# CarteMereM1_V2.net
KiCad netlist of a schematic drawn in EAGLE
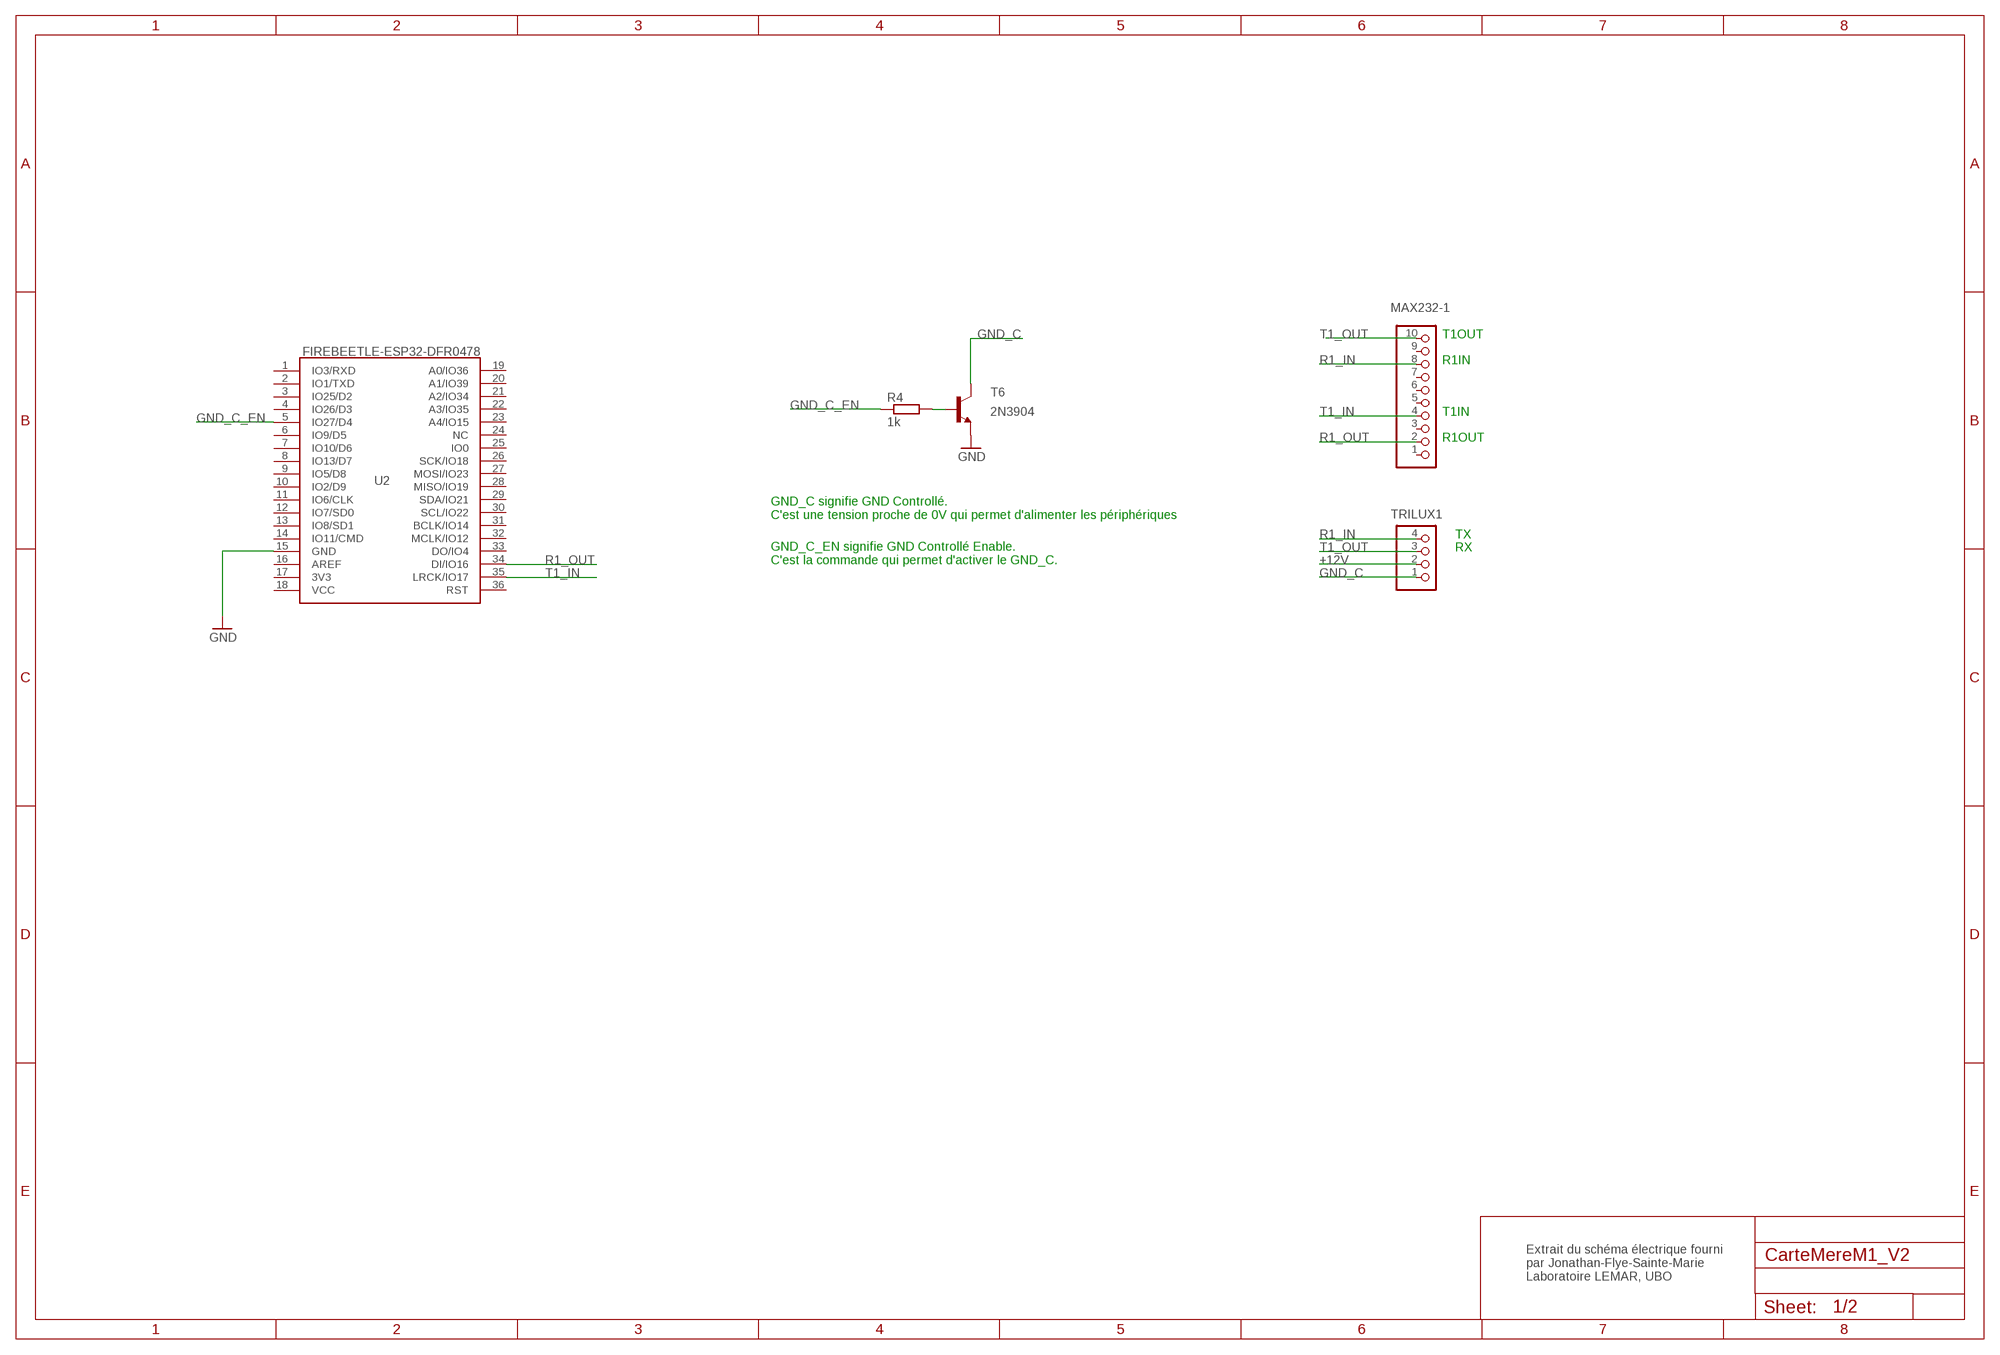
[diagram p0: schematic, sheet 1, part 1 of 2]
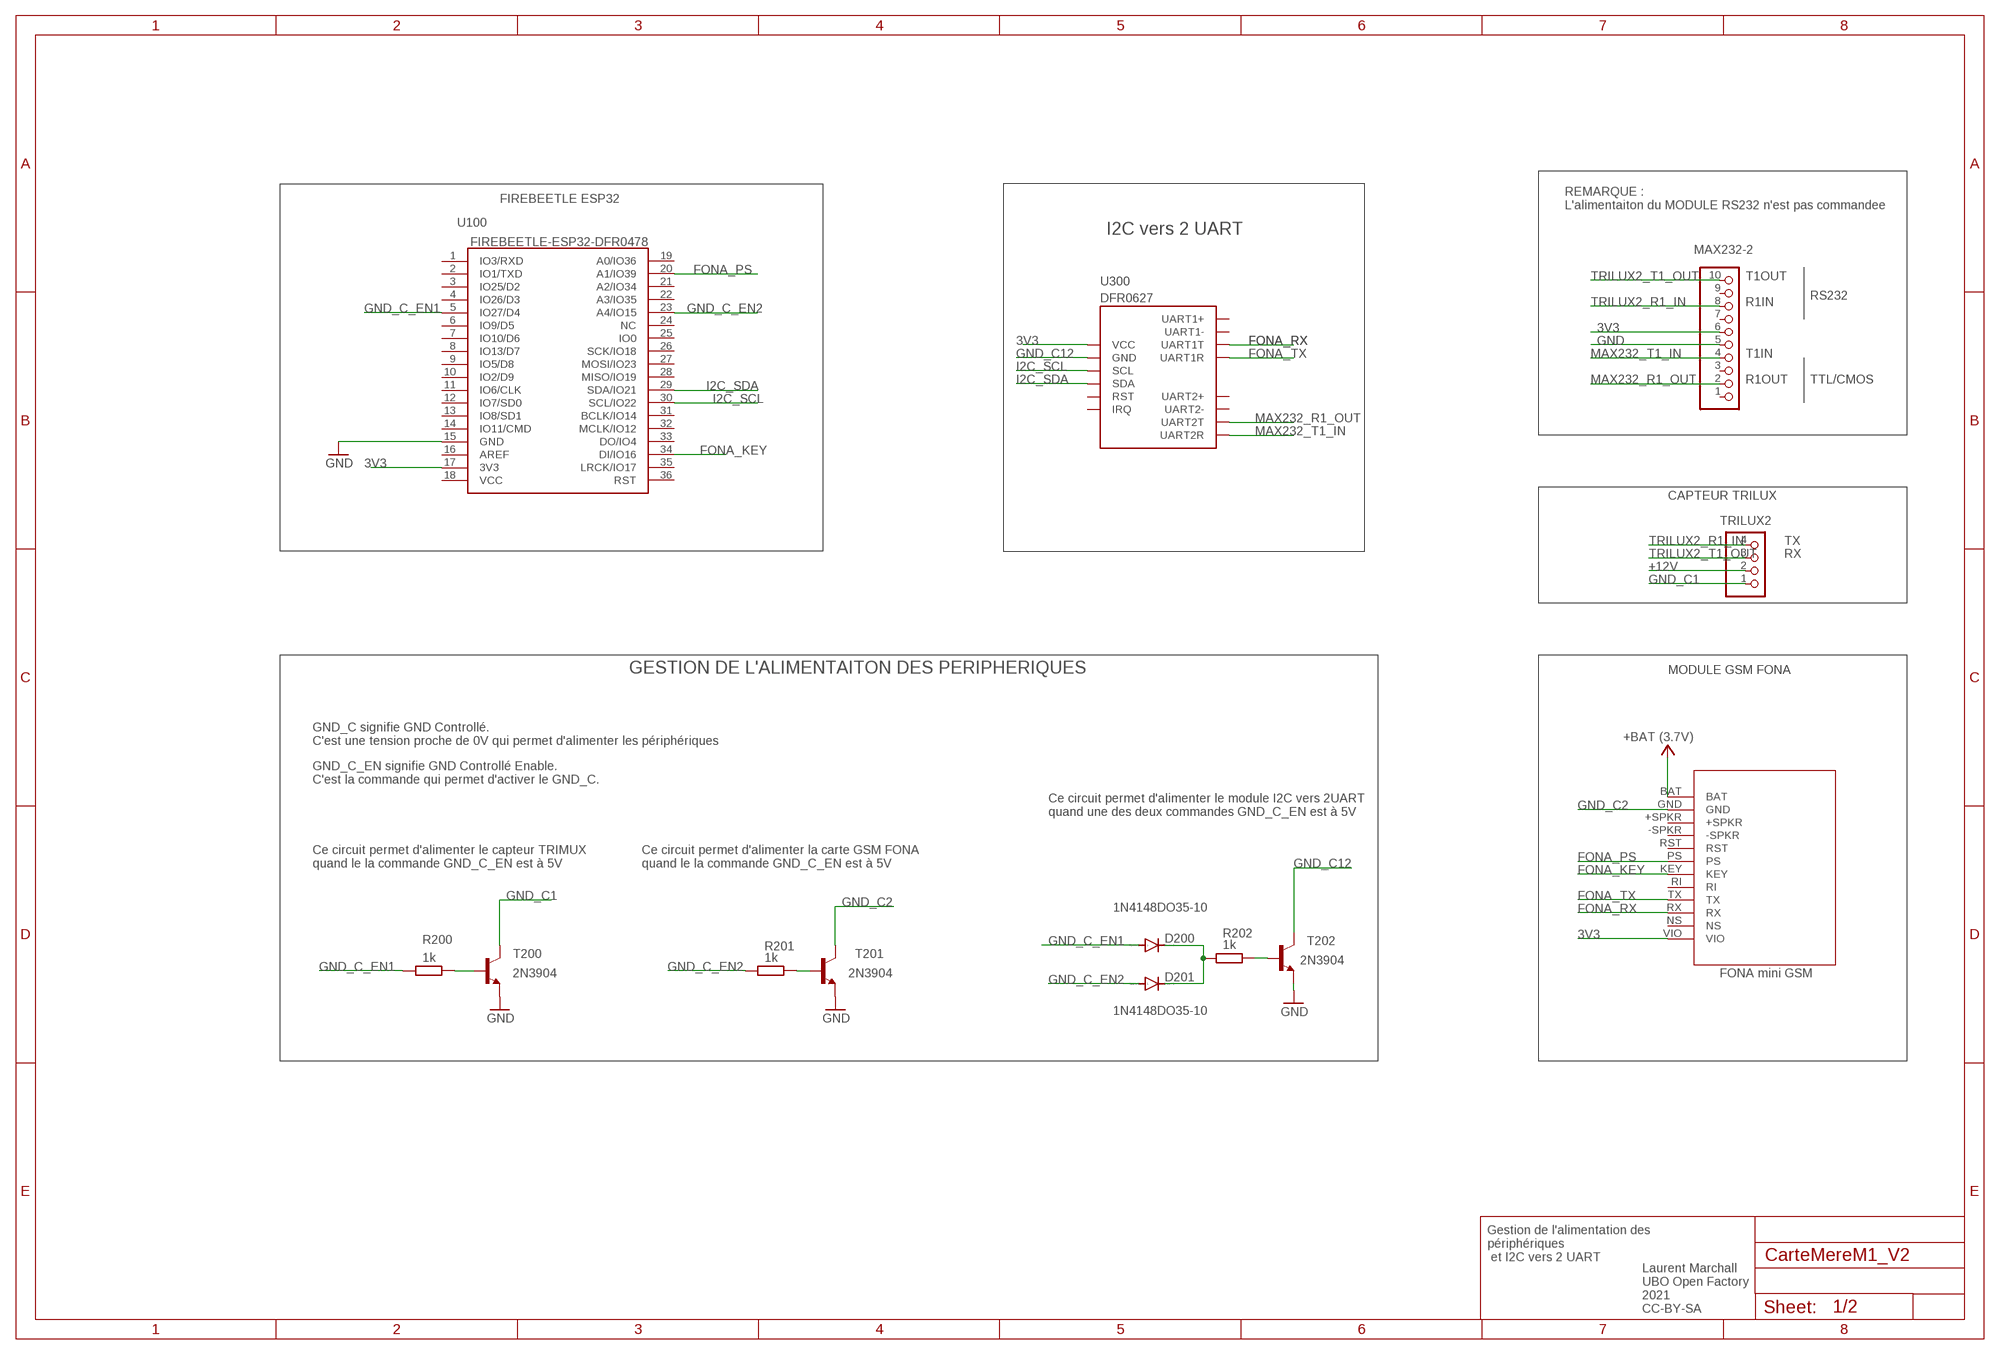
[diagram p1: schematic, sheet 1, part 2 of 2]

(export (version "E")
  (design (tool "Eeschema 10.0.6"))
  (components
    (comp (ref "D200")
      (value "1N4148DO35-10")
      (footprint "eagle-import:DO35-10")
      (libsource (lib "eagle-import") (part "1N4148DO35-10"))
    )
    (comp (ref "D201")
      (value "1N4148DO35-10")
      (footprint "eagle-import:DO35-10")
      (libsource (lib "eagle-import") (part "1N4148DO35-10"))
    )
    (comp (ref "MAX232-1")
      (value "PINHD-1X10")
      (footprint "eagle-import:1X10")
      (libsource (lib "eagle-import") (part "PINHD-1X10"))
    )
    (comp (ref "MAX232-2")
      (value "PINHD-1X10")
      (footprint "eagle-import:1X10")
      (libsource (lib "eagle-import") (part "PINHD-1X10"))
    )
    (comp (ref "R4")
      (value "1k")
      (footprint "eagle-import:0204_7")
      (libsource (lib "eagle-import") (part "R-EU_0204/7"))
    )
    (comp (ref "R200")
      (value "1k")
      (footprint "eagle-import:0204_7")
      (libsource (lib "eagle-import") (part "R-EU_0204/7"))
    )
    (comp (ref "R201")
      (value "1k")
      (footprint "eagle-import:0204_7")
      (libsource (lib "eagle-import") (part "R-EU_0204/7"))
    )
    (comp (ref "R202")
      (value "1k")
      (footprint "eagle-import:0204_7")
      (libsource (lib "eagle-import") (part "R-EU_0204/7"))
    )
    (comp (ref "T6")
      (value "2N3904")
      (footprint "eagle-import:TO92")
      (libsource (lib "eagle-import") (part "2N3904"))
    )
    (comp (ref "T200")
      (value "2N3904")
      (footprint "eagle-import:TO92")
      (libsource (lib "eagle-import") (part "2N3904"))
    )
    (comp (ref "T201")
      (value "2N3904")
      (footprint "eagle-import:TO92")
      (libsource (lib "eagle-import") (part "2N3904"))
    )
    (comp (ref "T202")
      (value "2N3904")
      (footprint "eagle-import:TO92")
      (libsource (lib "eagle-import") (part "2N3904"))
    )
    (comp (ref "TRILUX1")
      (value "PINHD-1X4")
      (footprint "eagle-import:1X04")
      (libsource (lib "eagle-import") (part "PINHD-1X4"))
    )
    (comp (ref "TRILUX2")
      (value "PINHD-1X4")
      (footprint "eagle-import:1X04")
      (libsource (lib "eagle-import") (part "PINHD-1X4"))
    )
    (comp (ref "U$1")
      (value "FONA_MINI_GSM")
      (footprint "eagle-import:FONA_MINI_GSM")
      (libsource (lib "eagle-import") (part "FONA_MINI_GSM"))
    )
    (comp (ref "U2")
      (value "FIREBEETLE-ESP32-DFR0478")
      (footprint "eagle-import:FIREBEETLE_ESP32")
      (fields
        (field (name "MANUFACTURER_PART_NUMBER") "DFR0478")
        (field (name "MOUSER_PART_NUMBER") "426-DFR0478")
      )
      (libsource (lib "eagle-import") (part "FIREBEETLE-ESP32-DFR0478"))
    )
    (comp (ref "U100")
      (value "FIREBEETLE-ESP32-DFR0478")
      (footprint "eagle-import:FIREBEETLE_ESP32")
      (fields
        (field (name "MANUFACTURER_PART_NUMBER") "DFR0478")
        (field (name "MOUSER_PART_NUMBER") "426-DFR0478")
      )
      (libsource (lib "eagle-import") (part "FIREBEETLE-ESP32-DFR0478"))
    )
    (comp (ref "U300")
      (value "DFR0627")
      (footprint "eagle-import:DUAL-UART-MODULE-DFR0627")
      (libsource (lib "eagle-import") (part "DUAL-UART-MODULE-DFR0627"))
    )
  )
  (nets
    (net (code "1") (name "+12V") (class "Default")
      (node (ref "TRILUX1") (pin "2") (pinfunction "2_2") (pintype "passive"))
      (node (ref "TRILUX2") (pin "2") (pinfunction "2_2") (pintype "passive"))
    )
    (net (code "2") (name "+BAT (3.7V)") (class "Default")
      (node (ref "U$1") (pin "BAT") (pinfunction "BAT_BAT") (pintype "power_in"))
    )
    (net (code "3") (name "3V3") (class "Default")
      (node (ref "MAX232-2") (pin "6") (pinfunction "6_6") (pintype "passive"))
      (node (ref "U$1") (pin "VIO") (pinfunction "VIO_VIO") (pintype "input"))
      (node (ref "U100") (pin "17") (pinfunction "3V3_17") (pintype "bidirectional"))
      (node (ref "U300") (pin "VCC") (pinfunction "VCC_VCC") (pintype "bidirectional"))
    )
    (net (code "4") (name "FONA_KEY") (class "Default")
      (node (ref "U$1") (pin "KEY") (pinfunction "KEY_KEY") (pintype "input"))
      (node (ref "U100") (pin "34") (pinfunction "DI/IO16_34") (pintype "bidirectional"))
    )
    (net (code "5") (name "FONA_PS") (class "Default")
      (node (ref "U$1") (pin "PS") (pinfunction "PS_PS") (pintype "output"))
      (node (ref "U100") (pin "20") (pinfunction "A1/IO39_20") (pintype "bidirectional"))
    )
    (net (code "6") (name "FONA_RX") (class "Default")
      (node (ref "U$1") (pin "RX") (pinfunction "RX_RX") (pintype "input"))
      (node (ref "U300") (pin "UART1T") (pinfunction "UART1T_UART1T") (pintype "bidirectional"))
    )
    (net (code "7") (name "FONA_TX") (class "Default")
      (node (ref "U$1") (pin "TX") (pinfunction "TX_TX") (pintype "output"))
      (node (ref "U300") (pin "UART1R") (pinfunction "UART1R_UART1R") (pintype "bidirectional"))
    )
    (net (code "8") (name "GND") (class "Default")
      (node (ref "MAX232-2") (pin "5") (pinfunction "5_5") (pintype "passive"))
      (node (ref "T200") (pin "3") (pinfunction "E_3") (pintype "passive"))
      (node (ref "T201") (pin "3") (pinfunction "E_3") (pintype "passive"))
      (node (ref "T202") (pin "3") (pinfunction "E_3") (pintype "passive"))
      (node (ref "T6") (pin "3") (pinfunction "E_3") (pintype "passive"))
      (node (ref "U100") (pin "15") (pinfunction "GND_15") (pintype "bidirectional"))
      (node (ref "U2") (pin "15") (pinfunction "GND_15") (pintype "bidirectional"))
    )
    (net (code "9") (name "GND_C") (class "Default")
      (node (ref "T6") (pin "1") (pinfunction "C_1") (pintype "passive"))
      (node (ref "TRILUX1") (pin "1") (pinfunction "1_1") (pintype "passive"))
    )
    (net (code "10") (name "GND_C1") (class "Default")
      (node (ref "T200") (pin "1") (pinfunction "C_1") (pintype "passive"))
      (node (ref "TRILUX2") (pin "1") (pinfunction "1_1") (pintype "passive"))
    )
    (net (code "11") (name "GND_C2") (class "Default")
      (node (ref "T201") (pin "1") (pinfunction "C_1") (pintype "passive"))
      (node (ref "U$1") (pin "GND") (pinfunction "GND_GND") (pintype "power_in"))
    )
    (net (code "12") (name "GND_C12") (class "Default")
      (node (ref "T202") (pin "1") (pinfunction "C_1") (pintype "passive"))
      (node (ref "U300") (pin "GND") (pinfunction "GND_GND") (pintype "bidirectional"))
    )
    (net (code "13") (name "GND_C_EN") (class "Default")
      (node (ref "R4") (pin "1") (pinfunction "1_1") (pintype "passive"))
      (node (ref "U2") (pin "5") (pinfunction "IO27/D4_5") (pintype "bidirectional"))
    )
    (net (code "14") (name "GND_C_EN1") (class "Default")
      (node (ref "D200") (pin "A") (pinfunction "A_A") (pintype "passive"))
      (node (ref "R200") (pin "1") (pinfunction "1_1") (pintype "passive"))
      (node (ref "U100") (pin "5") (pinfunction "IO27/D4_5") (pintype "bidirectional"))
    )
    (net (code "15") (name "GND_C_EN2") (class "Default")
      (node (ref "D201") (pin "A") (pinfunction "A_A") (pintype "passive"))
      (node (ref "R201") (pin "1") (pinfunction "1_1") (pintype "passive"))
      (node (ref "U100") (pin "23") (pinfunction "A4/IO15_23") (pintype "bidirectional"))
    )
    (net (code "16") (name "I2C_SCL") (class "Default")
      (node (ref "U100") (pin "30") (pinfunction "SCL/IO22_30") (pintype "bidirectional"))
      (node (ref "U300") (pin "SCL") (pinfunction "SCL_SCL") (pintype "bidirectional"))
    )
    (net (code "17") (name "I2C_SDA") (class "Default")
      (node (ref "U100") (pin "29") (pinfunction "SDA/IO21_29") (pintype "bidirectional"))
      (node (ref "U300") (pin "SDA") (pinfunction "SDA_SDA") (pintype "bidirectional"))
    )
    (net (code "18") (name "MAX232_R1_OUT") (class "Default")
      (node (ref "MAX232-2") (pin "2") (pinfunction "2_2") (pintype "passive"))
      (node (ref "U300") (pin "UART2T") (pinfunction "UART2T_UART2T") (pintype "bidirectional"))
    )
    (net (code "19") (name "MAX232_T1_IN") (class "Default")
      (node (ref "MAX232-2") (pin "4") (pinfunction "4_4") (pintype "passive"))
      (node (ref "U300") (pin "UART2R") (pinfunction "UART2R_UART2R") (pintype "bidirectional"))
    )
    (net (code "20") (name "Net-(D200-PadC)") (class "Default")
      (node (ref "D200") (pin "C") (pinfunction "C_C") (pintype "passive"))
      (node (ref "D201") (pin "C") (pinfunction "C_C") (pintype "passive"))
      (node (ref "R202") (pin "1") (pinfunction "1_1") (pintype "passive"))
    )
    (net (code "21") (name "Net-(T6-B)") (class "Default")
      (node (ref "R4") (pin "2") (pinfunction "2_2") (pintype "passive"))
      (node (ref "T6") (pin "2") (pinfunction "B_2") (pintype "passive"))
    )
    (net (code "22") (name "Net-(T200-B)") (class "Default")
      (node (ref "R200") (pin "2") (pinfunction "2_2") (pintype "passive"))
      (node (ref "T200") (pin "2") (pinfunction "B_2") (pintype "passive"))
    )
    (net (code "23") (name "Net-(T201-B)") (class "Default")
      (node (ref "R201") (pin "2") (pinfunction "2_2") (pintype "passive"))
      (node (ref "T201") (pin "2") (pinfunction "B_2") (pintype "passive"))
    )
    (net (code "24") (name "Net-(T202-B)") (class "Default")
      (node (ref "R202") (pin "2") (pinfunction "2_2") (pintype "passive"))
      (node (ref "T202") (pin "2") (pinfunction "B_2") (pintype "passive"))
    )
    (net (code "25") (name "R1_IN") (class "Default")
      (node (ref "MAX232-1") (pin "8") (pinfunction "8_8") (pintype "passive"))
      (node (ref "TRILUX1") (pin "4") (pinfunction "4_4") (pintype "passive"))
    )
    (net (code "26") (name "R1_OUT") (class "Default")
      (node (ref "MAX232-1") (pin "2") (pinfunction "2_2") (pintype "passive"))
      (node (ref "U2") (pin "34") (pinfunction "DI/IO16_34") (pintype "bidirectional"))
    )
    (net (code "27") (name "T1_IN") (class "Default")
      (node (ref "MAX232-1") (pin "4") (pinfunction "4_4") (pintype "passive"))
      (node (ref "U2") (pin "35") (pinfunction "LRCK/IO17_35") (pintype "bidirectional"))
    )
    (net (code "28") (name "T1_OUT") (class "Default")
      (node (ref "MAX232-1") (pin "10") (pinfunction "10_10") (pintype "passive"))
      (node (ref "TRILUX1") (pin "3") (pinfunction "3_3") (pintype "passive"))
    )
    (net (code "29") (name "TRILUX2_R1_IN") (class "Default")
      (node (ref "MAX232-2") (pin "8") (pinfunction "8_8") (pintype "passive"))
      (node (ref "TRILUX2") (pin "4") (pinfunction "4_4") (pintype "passive"))
    )
    (net (code "30") (name "TRILUX2_T1_OUT") (class "Default")
      (node (ref "MAX232-2") (pin "10") (pinfunction "10_10") (pintype "passive"))
      (node (ref "TRILUX2") (pin "3") (pinfunction "3_3") (pintype "passive"))
    )
    (net (code "31") (name "unconnected-(MAX232-1-Pad1)") (class "Default")
      (node (ref "MAX232-1") (pin "1") (pinfunction "1_1") (pintype "passive"))
    )
    (net (code "32") (name "unconnected-(MAX232-1-Pad3)") (class "Default")
      (node (ref "MAX232-1") (pin "3") (pinfunction "3_3") (pintype "passive"))
    )
    (net (code "33") (name "unconnected-(MAX232-1-Pad5)") (class "Default")
      (node (ref "MAX232-1") (pin "5") (pinfunction "5_5") (pintype "passive"))
    )
    (net (code "34") (name "unconnected-(MAX232-1-Pad6)") (class "Default")
      (node (ref "MAX232-1") (pin "6") (pinfunction "6_6") (pintype "passive"))
    )
    (net (code "35") (name "unconnected-(MAX232-1-Pad7)") (class "Default")
      (node (ref "MAX232-1") (pin "7") (pinfunction "7_7") (pintype "passive"))
    )
    (net (code "36") (name "unconnected-(MAX232-1-Pad9)") (class "Default")
      (node (ref "MAX232-1") (pin "9") (pinfunction "9_9") (pintype "passive"))
    )
    (net (code "37") (name "unconnected-(MAX232-2-Pad1)") (class "Default")
      (node (ref "MAX232-2") (pin "1") (pinfunction "1_1") (pintype "passive"))
    )
    (net (code "38") (name "unconnected-(MAX232-2-Pad3)") (class "Default")
      (node (ref "MAX232-2") (pin "3") (pinfunction "3_3") (pintype "passive"))
    )
    (net (code "39") (name "unconnected-(MAX232-2-Pad7)") (class "Default")
      (node (ref "MAX232-2") (pin "7") (pinfunction "7_7") (pintype "passive"))
    )
    (net (code "40") (name "unconnected-(MAX232-2-Pad9)") (class "Default")
      (node (ref "MAX232-2") (pin "9") (pinfunction "9_9") (pintype "passive"))
    )
    (net (code "41") (name "unconnected-(U$1-Pad+SPKR)") (class "Default")
      (node (ref "U$1") (pin "+SPKR") (pinfunction "+SPKR_+SPKR") (pintype "output"))
    )
    (net (code "42") (name "unconnected-(U$1-Pad-SPKR)") (class "Default")
      (node (ref "U$1") (pin "-SPKR") (pinfunction "-SPKR_-SPKR") (pintype "output"))
    )
    (net (code "43") (name "unconnected-(U$1-PadNS)") (class "Default")
      (node (ref "U$1") (pin "NS") (pinfunction "NS_NS") (pintype "output"))
    )
    (net (code "44") (name "unconnected-(U$1-PadRI)") (class "Default")
      (node (ref "U$1") (pin "RI") (pinfunction "RI_RI") (pintype "output"))
    )
    (net (code "45") (name "unconnected-(U$1-PadRST)") (class "Default")
      (node (ref "U$1") (pin "RST") (pinfunction "RST_RST") (pintype "input"))
    )
    (net (code "46") (name "unconnected-(U2-3V3-Pad17)") (class "Default")
      (node (ref "U2") (pin "17") (pinfunction "3V3_17") (pintype "bidirectional"))
    )
    (net (code "47") (name "unconnected-(U2-A0{slash}IO36-Pad19)") (class "Default")
      (node (ref "U2") (pin "19") (pinfunction "A0/IO36_19") (pintype "bidirectional"))
    )
    (net (code "48") (name "unconnected-(U2-A1{slash}IO39-Pad20)") (class "Default")
      (node (ref "U2") (pin "20") (pinfunction "A1/IO39_20") (pintype "bidirectional"))
    )
    (net (code "49") (name "unconnected-(U2-A2{slash}IO34-Pad21)") (class "Default")
      (node (ref "U2") (pin "21") (pinfunction "A2/IO34_21") (pintype "bidirectional"))
    )
    (net (code "50") (name "unconnected-(U2-A3{slash}IO35-Pad22)") (class "Default")
      (node (ref "U2") (pin "22") (pinfunction "A3/IO35_22") (pintype "bidirectional"))
    )
    (net (code "51") (name "unconnected-(U2-A4{slash}IO15-Pad23)") (class "Default")
      (node (ref "U2") (pin "23") (pinfunction "A4/IO15_23") (pintype "bidirectional"))
    )
    (net (code "52") (name "unconnected-(U2-AREF-Pad16)") (class "Default")
      (node (ref "U2") (pin "16") (pinfunction "AREF_16") (pintype "bidirectional"))
    )
    (net (code "53") (name "unconnected-(U2-BCLK{slash}IO14-Pad31)") (class "Default")
      (node (ref "U2") (pin "31") (pinfunction "BCLK/IO14_31") (pintype "bidirectional"))
    )
    (net (code "54") (name "unconnected-(U2-DO{slash}IO4-Pad33)") (class "Default")
      (node (ref "U2") (pin "33") (pinfunction "DO/IO4_33") (pintype "bidirectional"))
    )
    (net (code "55") (name "unconnected-(U2-IO0-Pad25)") (class "Default")
      (node (ref "U2") (pin "25") (pinfunction "IO0_25") (pintype "bidirectional"))
    )
    (net (code "56") (name "unconnected-(U2-IO1{slash}TXD-Pad2)") (class "Default")
      (node (ref "U2") (pin "2") (pinfunction "IO1/TXD_2") (pintype "bidirectional"))
    )
    (net (code "57") (name "unconnected-(U2-IO2{slash}D9-Pad10)") (class "Default")
      (node (ref "U2") (pin "10") (pinfunction "IO2/D9_10") (pintype "bidirectional"))
    )
    (net (code "58") (name "unconnected-(U2-IO3{slash}RXD-Pad1)") (class "Default")
      (node (ref "U2") (pin "1") (pinfunction "IO3/RXD_1") (pintype "bidirectional"))
    )
    (net (code "59") (name "unconnected-(U2-IO5{slash}D8-Pad9)") (class "Default")
      (node (ref "U2") (pin "9") (pinfunction "IO5/D8_9") (pintype "bidirectional"))
    )
    (net (code "60") (name "unconnected-(U2-IO6{slash}CLK-Pad11)") (class "Default")
      (node (ref "U2") (pin "11") (pinfunction "IO6/CLK_11") (pintype "bidirectional"))
    )
    (net (code "61") (name "unconnected-(U2-IO7{slash}SD0-Pad12)") (class "Default")
      (node (ref "U2") (pin "12") (pinfunction "IO7/SD0_12") (pintype "bidirectional"))
    )
    (net (code "62") (name "unconnected-(U2-IO8{slash}SD1-Pad13)") (class "Default")
      (node (ref "U2") (pin "13") (pinfunction "IO8/SD1_13") (pintype "bidirectional"))
    )
    (net (code "63") (name "unconnected-(U2-IO9{slash}D5-Pad6)") (class "Default")
      (node (ref "U2") (pin "6") (pinfunction "IO9/D5_6") (pintype "bidirectional"))
    )
    (net (code "64") (name "unconnected-(U2-IO10{slash}D6-Pad7)") (class "Default")
      (node (ref "U2") (pin "7") (pinfunction "IO10/D6_7") (pintype "bidirectional"))
    )
    (net (code "65") (name "unconnected-(U2-IO11{slash}CMD-Pad14)") (class "Default")
      (node (ref "U2") (pin "14") (pinfunction "IO11/CMD_14") (pintype "bidirectional"))
    )
    (net (code "66") (name "unconnected-(U2-IO13{slash}D7-Pad8)") (class "Default")
      (node (ref "U2") (pin "8") (pinfunction "IO13/D7_8") (pintype "bidirectional"))
    )
    (net (code "67") (name "unconnected-(U2-IO25{slash}D2-Pad3)") (class "Default")
      (node (ref "U2") (pin "3") (pinfunction "IO25/D2_3") (pintype "bidirectional"))
    )
    (net (code "68") (name "unconnected-(U2-IO26{slash}D3-Pad4)") (class "Default")
      (node (ref "U2") (pin "4") (pinfunction "IO26/D3_4") (pintype "bidirectional"))
    )
    (net (code "69") (name "unconnected-(U2-MCLK{slash}IO12-Pad32)") (class "Default")
      (node (ref "U2") (pin "32") (pinfunction "MCLK/IO12_32") (pintype "bidirectional"))
    )
    (net (code "70") (name "unconnected-(U2-MISO{slash}IO19-Pad28)") (class "Default")
      (node (ref "U2") (pin "28") (pinfunction "MISO/IO19_28") (pintype "bidirectional"))
    )
    (net (code "71") (name "unconnected-(U2-MOSI{slash}IO23-Pad27)") (class "Default")
      (node (ref "U2") (pin "27") (pinfunction "MOSI/IO23_27") (pintype "bidirectional"))
    )
    (net (code "72") (name "unconnected-(U2-NC-Pad24)") (class "Default")
      (node (ref "U2") (pin "24") (pinfunction "NC_24") (pintype "no_connect"))
    )
    (net (code "73") (name "unconnected-(U2-RST-Pad36)") (class "Default")
      (node (ref "U2") (pin "36") (pinfunction "RST_36") (pintype "bidirectional"))
    )
    (net (code "74") (name "unconnected-(U2-SCK{slash}IO18-Pad26)") (class "Default")
      (node (ref "U2") (pin "26") (pinfunction "SCK/IO18_26") (pintype "bidirectional"))
    )
    (net (code "75") (name "unconnected-(U2-SCL{slash}IO22-Pad30)") (class "Default")
      (node (ref "U2") (pin "30") (pinfunction "SCL/IO22_30") (pintype "bidirectional"))
    )
    (net (code "76") (name "unconnected-(U2-SDA{slash}IO21-Pad29)") (class "Default")
      (node (ref "U2") (pin "29") (pinfunction "SDA/IO21_29") (pintype "bidirectional"))
    )
    (net (code "77") (name "unconnected-(U2-VCC-Pad18)") (class "Default")
      (node (ref "U2") (pin "18") (pinfunction "VCC_18") (pintype "bidirectional"))
    )
    (net (code "78") (name "unconnected-(U100-A0{slash}IO36-Pad19)") (class "Default")
      (node (ref "U100") (pin "19") (pinfunction "A0/IO36_19") (pintype "bidirectional"))
    )
    (net (code "79") (name "unconnected-(U100-A2{slash}IO34-Pad21)") (class "Default")
      (node (ref "U100") (pin "21") (pinfunction "A2/IO34_21") (pintype "bidirectional"))
    )
    (net (code "80") (name "unconnected-(U100-A3{slash}IO35-Pad22)") (class "Default")
      (node (ref "U100") (pin "22") (pinfunction "A3/IO35_22") (pintype "bidirectional"))
    )
    (net (code "81") (name "unconnected-(U100-AREF-Pad16)") (class "Default")
      (node (ref "U100") (pin "16") (pinfunction "AREF_16") (pintype "bidirectional"))
    )
    (net (code "82") (name "unconnected-(U100-BCLK{slash}IO14-Pad31)") (class "Default")
      (node (ref "U100") (pin "31") (pinfunction "BCLK/IO14_31") (pintype "bidirectional"))
    )
    (net (code "83") (name "unconnected-(U100-DO{slash}IO4-Pad33)") (class "Default")
      (node (ref "U100") (pin "33") (pinfunction "DO/IO4_33") (pintype "bidirectional"))
    )
    (net (code "84") (name "unconnected-(U100-IO0-Pad25)") (class "Default")
      (node (ref "U100") (pin "25") (pinfunction "IO0_25") (pintype "bidirectional"))
    )
    (net (code "85") (name "unconnected-(U100-IO1{slash}TXD-Pad2)") (class "Default")
      (node (ref "U100") (pin "2") (pinfunction "IO1/TXD_2") (pintype "bidirectional"))
    )
    (net (code "86") (name "unconnected-(U100-IO2{slash}D9-Pad10)") (class "Default")
      (node (ref "U100") (pin "10") (pinfunction "IO2/D9_10") (pintype "bidirectional"))
    )
    (net (code "87") (name "unconnected-(U100-IO3{slash}RXD-Pad1)") (class "Default")
      (node (ref "U100") (pin "1") (pinfunction "IO3/RXD_1") (pintype "bidirectional"))
    )
    (net (code "88") (name "unconnected-(U100-IO5{slash}D8-Pad9)") (class "Default")
      (node (ref "U100") (pin "9") (pinfunction "IO5/D8_9") (pintype "bidirectional"))
    )
    (net (code "89") (name "unconnected-(U100-IO6{slash}CLK-Pad11)") (class "Default")
      (node (ref "U100") (pin "11") (pinfunction "IO6/CLK_11") (pintype "bidirectional"))
    )
    (net (code "90") (name "unconnected-(U100-IO7{slash}SD0-Pad12)") (class "Default")
      (node (ref "U100") (pin "12") (pinfunction "IO7/SD0_12") (pintype "bidirectional"))
    )
    (net (code "91") (name "unconnected-(U100-IO8{slash}SD1-Pad13)") (class "Default")
      (node (ref "U100") (pin "13") (pinfunction "IO8/SD1_13") (pintype "bidirectional"))
    )
    (net (code "92") (name "unconnected-(U100-IO9{slash}D5-Pad6)") (class "Default")
      (node (ref "U100") (pin "6") (pinfunction "IO9/D5_6") (pintype "bidirectional"))
    )
    (net (code "93") (name "unconnected-(U100-IO10{slash}D6-Pad7)") (class "Default")
      (node (ref "U100") (pin "7") (pinfunction "IO10/D6_7") (pintype "bidirectional"))
    )
    (net (code "94") (name "unconnected-(U100-IO11{slash}CMD-Pad14)") (class "Default")
      (node (ref "U100") (pin "14") (pinfunction "IO11/CMD_14") (pintype "bidirectional"))
    )
    (net (code "95") (name "unconnected-(U100-IO13{slash}D7-Pad8)") (class "Default")
      (node (ref "U100") (pin "8") (pinfunction "IO13/D7_8") (pintype "bidirectional"))
    )
    (net (code "96") (name "unconnected-(U100-IO25{slash}D2-Pad3)") (class "Default")
      (node (ref "U100") (pin "3") (pinfunction "IO25/D2_3") (pintype "bidirectional"))
    )
    (net (code "97") (name "unconnected-(U100-IO26{slash}D3-Pad4)") (class "Default")
      (node (ref "U100") (pin "4") (pinfunction "IO26/D3_4") (pintype "bidirectional"))
    )
    (net (code "98") (name "unconnected-(U100-LRCK{slash}IO17-Pad35)") (class "Default")
      (node (ref "U100") (pin "35") (pinfunction "LRCK/IO17_35") (pintype "bidirectional"))
    )
    (net (code "99") (name "unconnected-(U100-MCLK{slash}IO12-Pad32)") (class "Default")
      (node (ref "U100") (pin "32") (pinfunction "MCLK/IO12_32") (pintype "bidirectional"))
    )
    (net (code "100") (name "unconnected-(U100-MISO{slash}IO19-Pad28)") (class "Default")
      (node (ref "U100") (pin "28") (pinfunction "MISO/IO19_28") (pintype "bidirectional"))
    )
    (net (code "101") (name "unconnected-(U100-MOSI{slash}IO23-Pad27)") (class "Default")
      (node (ref "U100") (pin "27") (pinfunction "MOSI/IO23_27") (pintype "bidirectional"))
    )
    (net (code "102") (name "unconnected-(U100-NC-Pad24)") (class "Default")
      (node (ref "U100") (pin "24") (pinfunction "NC_24") (pintype "no_connect"))
    )
    (net (code "103") (name "unconnected-(U100-RST-Pad36)") (class "Default")
      (node (ref "U100") (pin "36") (pinfunction "RST_36") (pintype "bidirectional"))
    )
    (net (code "104") (name "unconnected-(U100-SCK{slash}IO18-Pad26)") (class "Default")
      (node (ref "U100") (pin "26") (pinfunction "SCK/IO18_26") (pintype "bidirectional"))
    )
    (net (code "105") (name "unconnected-(U100-VCC-Pad18)") (class "Default")
      (node (ref "U100") (pin "18") (pinfunction "VCC_18") (pintype "bidirectional"))
    )
    (net (code "106") (name "unconnected-(U300-PadIRQ)") (class "Default")
      (node (ref "U300") (pin "IRQ") (pinfunction "IRQ_IRQ") (pintype "bidirectional"))
    )
    (net (code "107") (name "unconnected-(U300-PadRST)") (class "Default")
      (node (ref "U300") (pin "RST") (pinfunction "RST_RST") (pintype "bidirectional"))
    )
    (net (code "108") (name "unconnected-(U300-PadUART1+)") (class "Default")
      (node (ref "U300") (pin "UART1+") (pinfunction "UART1+_UART1+") (pintype "bidirectional"))
    )
    (net (code "109") (name "unconnected-(U300-PadUART1-)") (class "Default")
      (node (ref "U300") (pin "UART1-") (pinfunction "UART1-_UART1-") (pintype "bidirectional"))
    )
    (net (code "110") (name "unconnected-(U300-PadUART2+)") (class "Default")
      (node (ref "U300") (pin "UART2+") (pinfunction "UART2+_UART2+") (pintype "bidirectional"))
    )
    (net (code "111") (name "unconnected-(U300-PadUART2-)") (class "Default")
      (node (ref "U300") (pin "UART2-") (pinfunction "UART2-_UART2-") (pintype "bidirectional"))
    )
  )
)
